# Sensors_AFE1.net
KiCad netlist of a schematic drawn in Altium Designer
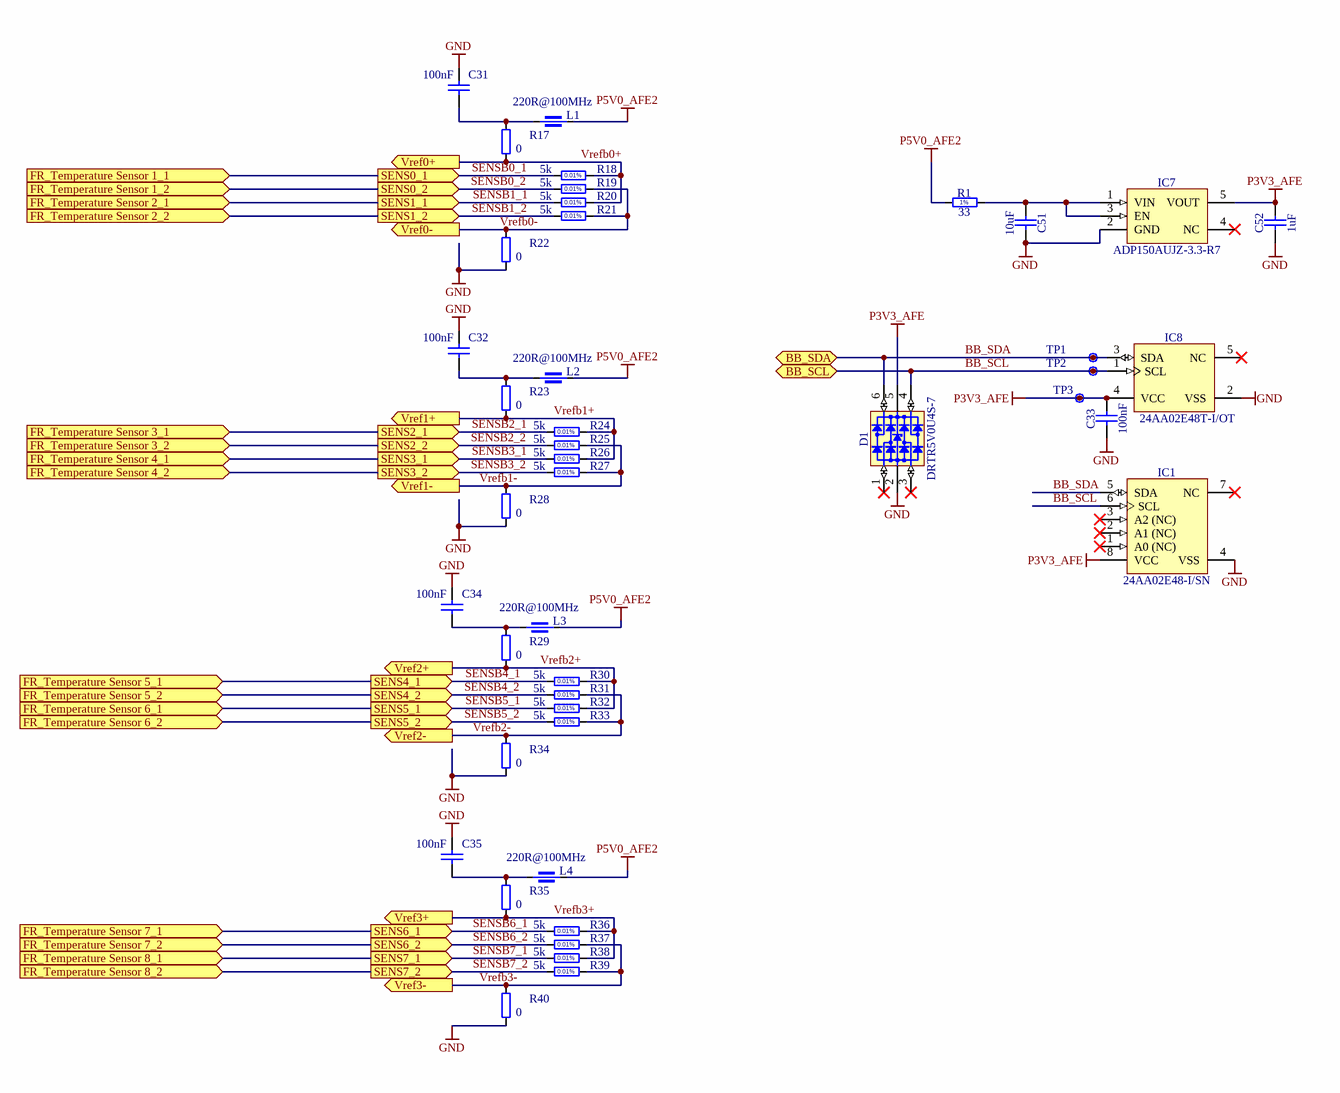
[diagram p0: Sensors_AFE1.schdoc]

(export (version "E")
  (design (tool "Eeschema 10.0.6"))
  (components
    (comp (ref "C31")
      (value "100nF")
      (footprint "CAPC1005X55N")
      (description "Non-polarised capacitor")
      (fields
        (field (name "PART NUMBER") "CC0402_100NF_16V_10%_X5R")
        (field (name "VOLTAGE") "16V")
        (field (name "AUTHOR") "CERN DEM JLC")
      )
      (libsource (lib "Capacitors") (part "Capacitor - non polarized"))
    )
    (comp (ref "C32")
      (value "100nF")
      (footprint "CAPC1005X55N")
      (description "Non-polarised capacitor")
      (fields
        (field (name "PART NUMBER") "CC0402_100NF_16V_10%_X5R")
        (field (name "VOLTAGE") "16V")
        (field (name "AUTHOR") "CERN DEM JLC")
      )
      (libsource (lib "Capacitors") (part "Capacitor - non polarized"))
    )
    (comp (ref "C33")
      (value "100nF")
      (footprint "CAPC1005X55N")
      (description "Non-polarised capacitor")
      (fields
        (field (name "PART NUMBER") "CC0402_100NF_16V_10%_X5R")
        (field (name "VOLTAGE") "16V")
        (field (name "AUTHOR") "CERN DEM JLC")
      )
      (libsource (lib "Capacitors") (part "Capacitor - non polarized"))
    )
    (comp (ref "C34")
      (value "100nF")
      (footprint "CAPC1005X55N")
      (description "Non-polarised capacitor")
      (fields
        (field (name "PART NUMBER") "CC0402_100NF_16V_10%_X5R")
        (field (name "VOLTAGE") "16V")
        (field (name "AUTHOR") "CERN DEM JLC")
      )
      (libsource (lib "Capacitors") (part "Capacitor - non polarized"))
    )
    (comp (ref "C35")
      (value "100nF")
      (footprint "CAPC1005X55N")
      (description "Non-polarised capacitor")
      (fields
        (field (name "PART NUMBER") "CC0402_100NF_16V_10%_X5R")
        (field (name "VOLTAGE") "16V")
        (field (name "AUTHOR") "CERN DEM JLC")
      )
      (libsource (lib "Capacitors") (part "Capacitor - non polarized"))
    )
    (comp (ref "C51")
      (value "10uF")
      (footprint "CAPC2012X135N")
      (description "Non-polarised capacitor")
      (fields
        (field (name "PART NUMBER") "CC0805_10UF_16V_10%_X5R")
        (field (name "VOLTAGE") "16V")
        (field (name "AUTHOR") "CERN DEM JLC")
      )
      (libsource (lib "Capacitors") (part "Capacitor - non polarized"))
    )
    (comp (ref "C52")
      (value "1uF")
      (footprint "CAPC1608X87N")
      (description "Non-polarised capacitor")
      (fields
        (field (name "PART NUMBER") "CC0603_1UF_25V_10%_X7R")
        (field (name "VOLTAGE") "25V")
        (field (name "AUTHOR") "CERN DEM JLC")
      )
      (libsource (lib "Capacitors") (part "Capacitor - non polarized"))
    )
    (comp (ref "D1")
      (value "DRTR5V0U4S-7")
      (footprint "SOT65P210X110-6N")
      (description "Integrated Quad Ultra-Low Capacitance ESD Protection")
      (fields (field (name "MANUFACTURER") "DIODES") (field (name "AUTHOR") "GK"))
      (libsource (lib "Diodes") (part "D_TVS_DRTR5V0U4S-7"))
    )
    (comp (ref "IC1")
      (value "24AA02E48-I/SN")
      (footprint "SOIC127P600X175-8N")
      (description "1.7V-5.5V, 2K I2C™ Serial EEPROMs with EUI-48™ Node Identity")
      (fields (field (name "MANUFACTURER") "MICROCHIP TECHNOLOGY") (field (name "AUTHOR") "CERN DEM MR"))
      (libsource (lib "ICS-logic") (part "MEM_24AA02E48-I/SN"))
    )
    (comp (ref "IC7")
      (value "ADP150AUJZ-3.3-R7")
      (footprint "SOT95P280X90-5N")
      (description "Ultralow Noise, 150 mA CMOS Linear Regulator")
      (fields (field (name "MANUFACTURER") "ANALOG DEVICES") (field (name "AUTHOR") "CERN DEM JLC"))
      (libsource (lib "ICs And Semiconductors") (part "ADP150AUJZ"))
    )
    (comp (ref "IC8")
      (value "24AA02E48T-I/OT")
      (footprint "SOT95P280X145-5N")
      (description "1.7V-5.5V, 2K I2C Serial EEPROM With EUI-48 Node Identity")
      (fields (field (name "MANUFACTURER") "MICROCHIP TECHNOLOGY") (field (name "AUTHOR") "CERN DEM MR"))
      (libsource (lib "ICs And Semiconductors") (part "24AA02E48T-I/OT"))
    )
    (comp (ref "L1")
      (value "220R@100MHz")
      (footprint "INDC1005X55N")
      (fields
        (field (name "PART NUMBER") "IND0402_MURATA_BLM15HB221SN1")
        (field (name "POWER") "250mA")
        (field (name "TOLERANCE") "±25%")
        (field (name "AUTHOR") "CERN DEM JLC")
      )
      (libsource (lib "Inductors & Transformers") (part "Ferrite Bead"))
    )
    (comp (ref "L2")
      (value "220R@100MHz")
      (footprint "INDC1005X55N")
      (fields
        (field (name "PART NUMBER") "IND0402_MURATA_BLM15HB221SN1")
        (field (name "POWER") "250mA")
        (field (name "TOLERANCE") "±25%")
        (field (name "AUTHOR") "CERN DEM JLC")
      )
      (libsource (lib "Inductors & Transformers") (part "Ferrite Bead"))
    )
    (comp (ref "L3")
      (value "220R@100MHz")
      (footprint "INDC1005X55N")
      (fields
        (field (name "PART NUMBER") "IND0402_MURATA_BLM15HB221SN1")
        (field (name "POWER") "250mA")
        (field (name "TOLERANCE") "±25%")
        (field (name "AUTHOR") "CERN DEM JLC")
      )
      (libsource (lib "Inductors & Transformers") (part "Ferrite Bead"))
    )
    (comp (ref "L4")
      (value "220R@100MHz")
      (footprint "INDC1005X55N")
      (fields
        (field (name "PART NUMBER") "IND0402_MURATA_BLM15HB221SN1")
        (field (name "POWER") "250mA")
        (field (name "TOLERANCE") "±25%")
        (field (name "AUTHOR") "CERN DEM JLC")
      )
      (libsource (lib "Inductors & Transformers") (part "Ferrite Bead"))
    )
    (comp (ref "R1")
      (value "33")
      (footprint "RESC1005X40N")
      (description "Resistor - 1%")
      (fields
        (field (name "PART NUMBER") "R0402_33R_1%_0.0625W_100PPM")
        (field (name "POWER") "0.0625W")
        (field (name "AUTHOR") "CERN DEM JLC")
      )
      (libsource (lib "Resistors") (part "Resistor - 1%"))
    )
    (comp (ref "R17")
      (value "0")
      (footprint "RESC1608X55N")
      (description "Resistor")
      (fields
        (field (name "PART NUMBER") "R0603_0R_JUMPER")
        (field (name "MANUFACTURER") "GENERIC")
        (field (name "AUTHOR") "CERN DEM JLC")
      )
      (libsource (lib "Resistors") (part "Resistor"))
    )
    (comp (ref "R18")
      (value "5k")
      (footprint "RESC2013X64N")
      (description "Resistor - 0.01%")
      (fields
        (field (name "PART NUMBER") "R0805_5K_0.01%_0.2W_0.2PPM_VISHAY_VSMP")
        (field (name "POWER") "0.2W")
        (field (name "AUTHOR") "CERN DEM JLC")
      )
      (libsource (lib "Resistors") (part "Resistor - 0.01%"))
    )
    (comp (ref "R19")
      (value "5k")
      (footprint "RESC2013X64N")
      (description "Resistor - 0.01%")
      (fields
        (field (name "PART NUMBER") "R0805_5K_0.01%_0.2W_0.2PPM_VISHAY_VSMP")
        (field (name "POWER") "0.2W")
        (field (name "AUTHOR") "CERN DEM JLC")
      )
      (libsource (lib "Resistors") (part "Resistor - 0.01%"))
    )
    (comp (ref "R20")
      (value "5k")
      (footprint "RESC2013X64N")
      (description "Resistor - 0.01%")
      (fields
        (field (name "PART NUMBER") "R0805_5K_0.01%_0.2W_0.2PPM_VISHAY_VSMP")
        (field (name "POWER") "0.2W")
        (field (name "AUTHOR") "CERN DEM JLC")
      )
      (libsource (lib "Resistors") (part "Resistor - 0.01%"))
    )
    (comp (ref "R21")
      (value "5k")
      (footprint "RESC2013X64N")
      (description "Resistor - 0.01%")
      (fields
        (field (name "PART NUMBER") "R0805_5K_0.01%_0.2W_0.2PPM_VISHAY_VSMP")
        (field (name "POWER") "0.2W")
        (field (name "AUTHOR") "CERN DEM JLC")
      )
      (libsource (lib "Resistors") (part "Resistor - 0.01%"))
    )
    (comp (ref "R22")
      (value "0")
      (footprint "RESC1608X55N")
      (description "Resistor")
      (fields
        (field (name "PART NUMBER") "R0603_0R_JUMPER")
        (field (name "MANUFACTURER") "GENERIC")
        (field (name "AUTHOR") "CERN DEM JLC")
      )
      (libsource (lib "Resistors") (part "Resistor"))
    )
    (comp (ref "R23")
      (value "0")
      (footprint "RESC1608X55N")
      (description "Resistor")
      (fields
        (field (name "PART NUMBER") "R0603_0R_JUMPER")
        (field (name "MANUFACTURER") "GENERIC")
        (field (name "AUTHOR") "CERN DEM JLC")
      )
      (libsource (lib "Resistors") (part "Resistor"))
    )
    (comp (ref "R24")
      (value "5k")
      (footprint "RESC2013X64N")
      (description "Resistor - 0.01%")
      (fields
        (field (name "PART NUMBER") "R0805_5K_0.01%_0.2W_0.2PPM_VISHAY_VSMP")
        (field (name "POWER") "0.2W")
        (field (name "AUTHOR") "CERN DEM JLC")
      )
      (libsource (lib "Resistors") (part "Resistor - 0.01%"))
    )
    (comp (ref "R25")
      (value "5k")
      (footprint "RESC2013X64N")
      (description "Resistor - 0.01%")
      (fields
        (field (name "PART NUMBER") "R0805_5K_0.01%_0.2W_0.2PPM_VISHAY_VSMP")
        (field (name "POWER") "0.2W")
        (field (name "AUTHOR") "CERN DEM JLC")
      )
      (libsource (lib "Resistors") (part "Resistor - 0.01%"))
    )
    (comp (ref "R26")
      (value "5k")
      (footprint "RESC2013X64N")
      (description "Resistor - 0.01%")
      (fields
        (field (name "PART NUMBER") "R0805_5K_0.01%_0.2W_0.2PPM_VISHAY_VSMP")
        (field (name "POWER") "0.2W")
        (field (name "AUTHOR") "CERN DEM JLC")
      )
      (libsource (lib "Resistors") (part "Resistor - 0.01%"))
    )
    (comp (ref "R27")
      (value "5k")
      (footprint "RESC2013X64N")
      (description "Resistor - 0.01%")
      (fields
        (field (name "PART NUMBER") "R0805_5K_0.01%_0.2W_0.2PPM_VISHAY_VSMP")
        (field (name "POWER") "0.2W")
        (field (name "AUTHOR") "CERN DEM JLC")
      )
      (libsource (lib "Resistors") (part "Resistor - 0.01%"))
    )
    (comp (ref "R28")
      (value "0")
      (footprint "RESC1608X55N")
      (description "Resistor")
      (fields
        (field (name "PART NUMBER") "R0603_0R_JUMPER")
        (field (name "MANUFACTURER") "GENERIC")
        (field (name "AUTHOR") "CERN DEM JLC")
      )
      (libsource (lib "Resistors") (part "Resistor"))
    )
    (comp (ref "R29")
      (value "0")
      (footprint "RESC1608X55N")
      (description "Resistor")
      (fields
        (field (name "PART NUMBER") "R0603_0R_JUMPER")
        (field (name "MANUFACTURER") "GENERIC")
        (field (name "AUTHOR") "CERN DEM JLC")
      )
      (libsource (lib "Resistors") (part "Resistor"))
    )
    (comp (ref "R30")
      (value "5k")
      (footprint "RESC2013X64N")
      (description "Resistor - 0.01%")
      (fields
        (field (name "PART NUMBER") "R0805_5K_0.01%_0.2W_0.2PPM_VISHAY_VSMP")
        (field (name "POWER") "0.2W")
        (field (name "AUTHOR") "CERN DEM JLC")
      )
      (libsource (lib "Resistors") (part "Resistor - 0.01%"))
    )
    (comp (ref "R31")
      (value "5k")
      (footprint "RESC2013X64N")
      (description "Resistor - 0.01%")
      (fields
        (field (name "PART NUMBER") "R0805_5K_0.01%_0.2W_0.2PPM_VISHAY_VSMP")
        (field (name "POWER") "0.2W")
        (field (name "AUTHOR") "CERN DEM JLC")
      )
      (libsource (lib "Resistors") (part "Resistor - 0.01%"))
    )
    (comp (ref "R32")
      (value "5k")
      (footprint "RESC2013X64N")
      (description "Resistor - 0.01%")
      (fields
        (field (name "PART NUMBER") "R0805_5K_0.01%_0.2W_0.2PPM_VISHAY_VSMP")
        (field (name "POWER") "0.2W")
        (field (name "AUTHOR") "CERN DEM JLC")
      )
      (libsource (lib "Resistors") (part "Resistor - 0.01%"))
    )
    (comp (ref "R33")
      (value "5k")
      (footprint "RESC2013X64N")
      (description "Resistor - 0.01%")
      (fields
        (field (name "PART NUMBER") "R0805_5K_0.01%_0.2W_0.2PPM_VISHAY_VSMP")
        (field (name "POWER") "0.2W")
        (field (name "AUTHOR") "CERN DEM JLC")
      )
      (libsource (lib "Resistors") (part "Resistor - 0.01%"))
    )
    (comp (ref "R34")
      (value "0")
      (footprint "RESC1608X55N")
      (description "Resistor")
      (fields
        (field (name "PART NUMBER") "R0603_0R_JUMPER")
        (field (name "MANUFACTURER") "GENERIC")
        (field (name "AUTHOR") "CERN DEM JLC")
      )
      (libsource (lib "Resistors") (part "Resistor"))
    )
    (comp (ref "R35")
      (value "0")
      (footprint "RESC1608X55N")
      (description "Resistor")
      (fields
        (field (name "PART NUMBER") "R0603_0R_JUMPER")
        (field (name "MANUFACTURER") "GENERIC")
        (field (name "AUTHOR") "CERN DEM JLC")
      )
      (libsource (lib "Resistors") (part "Resistor"))
    )
    (comp (ref "R36")
      (value "5k")
      (footprint "RESC2013X64N")
      (description "Resistor - 0.01%")
      (fields
        (field (name "PART NUMBER") "R0805_5K_0.01%_0.2W_0.2PPM_VISHAY_VSMP")
        (field (name "POWER") "0.2W")
        (field (name "AUTHOR") "CERN DEM JLC")
      )
      (libsource (lib "Resistors") (part "Resistor - 0.01%"))
    )
    (comp (ref "R37")
      (value "5k")
      (footprint "RESC2013X64N")
      (description "Resistor - 0.01%")
      (fields
        (field (name "PART NUMBER") "R0805_5K_0.01%_0.2W_0.2PPM_VISHAY_VSMP")
        (field (name "POWER") "0.2W")
        (field (name "AUTHOR") "CERN DEM JLC")
      )
      (libsource (lib "Resistors") (part "Resistor - 0.01%"))
    )
    (comp (ref "R38")
      (value "5k")
      (footprint "RESC2013X64N")
      (description "Resistor - 0.01%")
      (fields
        (field (name "PART NUMBER") "R0805_5K_0.01%_0.2W_0.2PPM_VISHAY_VSMP")
        (field (name "POWER") "0.2W")
        (field (name "AUTHOR") "CERN DEM JLC")
      )
      (libsource (lib "Resistors") (part "Resistor - 0.01%"))
    )
    (comp (ref "R39")
      (value "5k")
      (footprint "RESC2013X64N")
      (description "Resistor - 0.01%")
      (fields
        (field (name "PART NUMBER") "R0805_5K_0.01%_0.2W_0.2PPM_VISHAY_VSMP")
        (field (name "POWER") "0.2W")
        (field (name "AUTHOR") "CERN DEM JLC")
      )
      (libsource (lib "Resistors") (part "Resistor - 0.01%"))
    )
    (comp (ref "R40")
      (value "0")
      (footprint "RESC1608X55N")
      (description "Resistor")
      (fields
        (field (name "PART NUMBER") "R0603_0R_JUMPER")
        (field (name "MANUFACTURER") "GENERIC")
        (field (name "AUTHOR") "CERN DEM JLC")
      )
      (libsource (lib "Resistors") (part "Resistor"))
    )
    (comp (ref "TP1")
      (value "Test Point")
      (footprint "TPS127")
      (fields (field (name "PART NUMBER") "SMD_PAD_1.27X1.27MM") (field (name "AUTHOR") "CERN DEM JLC"))
      (libsource (lib "Eletro-mechanical") (part "Test Point"))
    )
    (comp (ref "TP2")
      (value "Test Point")
      (footprint "TPS127")
      (fields (field (name "PART NUMBER") "SMD_PAD_1.27X1.27MM") (field (name "AUTHOR") "CERN DEM JLC"))
      (libsource (lib "Eletro-mechanical") (part "Test Point"))
    )
    (comp (ref "TP3")
      (value "Test Point")
      (footprint "TPS127")
      (fields (field (name "PART NUMBER") "SMD_PAD_1.27X1.27MM") (field (name "AUTHOR") "CERN DEM JLC"))
      (libsource (lib "Eletro-mechanical") (part "Test Point"))
    )
  )
  (nets
    (net (code "1") (name "/BB_SCL") (class "Default")
      (node (ref "D1") (pin "4") (pinfunction "I/O3_4") (pintype "bidirectional"))
      (node (ref "IC1") (pin "6") (pinfunction "SCL_6") (pintype "input"))
      (node (ref "IC8") (pin "1") (pinfunction "SCL_1") (pintype "input"))
      (node (ref "TP2") (pin "1") (pinfunction "1_1") (pintype "bidirectional"))
    )
    (net (code "2") (name "/BB_SDA") (class "Default")
      (node (ref "D1") (pin "6") (pinfunction "I/O4_6") (pintype "bidirectional"))
      (node (ref "IC1") (pin "5") (pinfunction "SDA_5") (pintype "bidirectional"))
      (node (ref "IC8") (pin "3") (pinfunction "SDA_3") (pintype "bidirectional"))
      (node (ref "TP1") (pin "1") (pinfunction "1_1") (pintype "bidirectional"))
    )
    (net (code "3") (name "/SENSB0_1") (class "Default")
      (node (ref "R18") (pin "1") (pinfunction "1_1") (pintype "passive"))
    )
    (net (code "4") (name "/SENSB0_2") (class "Default")
      (node (ref "R19") (pin "1") (pinfunction "1_1") (pintype "passive"))
    )
    (net (code "5") (name "/SENSB1_1") (class "Default")
      (node (ref "R20") (pin "1") (pinfunction "1_1") (pintype "passive"))
    )
    (net (code "6") (name "/SENSB1_2") (class "Default")
      (node (ref "R21") (pin "1") (pinfunction "1_1") (pintype "passive"))
    )
    (net (code "7") (name "/SENSB2_1") (class "Default")
      (node (ref "R24") (pin "1") (pinfunction "1_1") (pintype "passive"))
    )
    (net (code "8") (name "/SENSB2_2") (class "Default")
      (node (ref "R25") (pin "1") (pinfunction "1_1") (pintype "passive"))
    )
    (net (code "9") (name "/SENSB3_1") (class "Default")
      (node (ref "R26") (pin "1") (pinfunction "1_1") (pintype "passive"))
    )
    (net (code "10") (name "/SENSB3_2") (class "Default")
      (node (ref "R27") (pin "1") (pinfunction "1_1") (pintype "passive"))
    )
    (net (code "11") (name "/SENSB4_1") (class "Default")
      (node (ref "R30") (pin "1") (pinfunction "1_1") (pintype "passive"))
    )
    (net (code "12") (name "/SENSB4_2") (class "Default")
      (node (ref "R31") (pin "1") (pinfunction "1_1") (pintype "passive"))
    )
    (net (code "13") (name "/SENSB5_1") (class "Default")
      (node (ref "R32") (pin "1") (pinfunction "1_1") (pintype "passive"))
    )
    (net (code "14") (name "/SENSB5_2") (class "Default")
      (node (ref "R33") (pin "1") (pinfunction "1_1") (pintype "passive"))
    )
    (net (code "15") (name "/SENSB6_1") (class "Default")
      (node (ref "R36") (pin "1") (pinfunction "1_1") (pintype "passive"))
    )
    (net (code "16") (name "/SENSB6_2") (class "Default")
      (node (ref "R37") (pin "1") (pinfunction "1_1") (pintype "passive"))
    )
    (net (code "17") (name "/SENSB7_1") (class "Default")
      (node (ref "R38") (pin "1") (pinfunction "1_1") (pintype "passive"))
    )
    (net (code "18") (name "/SENSB7_2") (class "Default")
      (node (ref "R39") (pin "1") (pinfunction "1_1") (pintype "passive"))
    )
    (net (code "19") (name "/Vrefb0+") (class "Default")
      (node (ref "R17") (pin "1") (pinfunction "1_1") (pintype "passive"))
      (node (ref "R18") (pin "2") (pinfunction "2_2") (pintype "passive"))
      (node (ref "R20") (pin "2") (pinfunction "2_2") (pintype "passive"))
    )
    (net (code "20") (name "/Vrefb0-") (class "Default")
      (node (ref "R19") (pin "2") (pinfunction "2_2") (pintype "passive"))
      (node (ref "R21") (pin "2") (pinfunction "2_2") (pintype "passive"))
      (node (ref "R22") (pin "2") (pinfunction "2_2") (pintype "passive"))
    )
    (net (code "21") (name "/Vrefb1+") (class "Default")
      (node (ref "R23") (pin "1") (pinfunction "1_1") (pintype "passive"))
      (node (ref "R24") (pin "2") (pinfunction "2_2") (pintype "passive"))
      (node (ref "R26") (pin "2") (pinfunction "2_2") (pintype "passive"))
    )
    (net (code "22") (name "/Vrefb1-") (class "Default")
      (node (ref "R25") (pin "2") (pinfunction "2_2") (pintype "passive"))
      (node (ref "R27") (pin "2") (pinfunction "2_2") (pintype "passive"))
      (node (ref "R28") (pin "2") (pinfunction "2_2") (pintype "passive"))
    )
    (net (code "23") (name "/Vrefb2+") (class "Default")
      (node (ref "R29") (pin "1") (pinfunction "1_1") (pintype "passive"))
      (node (ref "R30") (pin "2") (pinfunction "2_2") (pintype "passive"))
      (node (ref "R32") (pin "2") (pinfunction "2_2") (pintype "passive"))
    )
    (net (code "24") (name "/Vrefb2-") (class "Default")
      (node (ref "R31") (pin "2") (pinfunction "2_2") (pintype "passive"))
      (node (ref "R33") (pin "2") (pinfunction "2_2") (pintype "passive"))
      (node (ref "R34") (pin "2") (pinfunction "2_2") (pintype "passive"))
    )
    (net (code "25") (name "/Vrefb3+") (class "Default")
      (node (ref "R35") (pin "1") (pinfunction "1_1") (pintype "passive"))
      (node (ref "R36") (pin "2") (pinfunction "2_2") (pintype "passive"))
      (node (ref "R38") (pin "2") (pinfunction "2_2") (pintype "passive"))
    )
    (net (code "26") (name "/Vrefb3-") (class "Default")
      (node (ref "R37") (pin "2") (pinfunction "2_2") (pintype "passive"))
      (node (ref "R39") (pin "2") (pinfunction "2_2") (pintype "passive"))
      (node (ref "R40") (pin "2") (pinfunction "2_2") (pintype "passive"))
    )
    (net (code "27") (name "GND") (class "Default")
      (node (ref "C31") (pin "1") (pinfunction "1_1") (pintype "passive"))
      (node (ref "C32") (pin "1") (pinfunction "1_1") (pintype "passive"))
      (node (ref "C33") (pin "1") (pinfunction "1_1") (pintype "passive"))
      (node (ref "C34") (pin "1") (pinfunction "1_1") (pintype "passive"))
      (node (ref "C35") (pin "1") (pinfunction "1_1") (pintype "passive"))
      (node (ref "C51") (pin "2") (pinfunction "2_2") (pintype "passive"))
      (node (ref "C52") (pin "1") (pinfunction "1_1") (pintype "passive"))
      (node (ref "D1") (pin "2") (pinfunction "GND_2") (pintype "power_in"))
      (node (ref "IC1") (pin "4") (pinfunction "VSS_4") (pintype "power_in"))
      (node (ref "IC7") (pin "2") (pinfunction "GND_2") (pintype "power_in"))
      (node (ref "IC8") (pin "2") (pinfunction "VSS_2") (pintype "power_in"))
      (node (ref "R22") (pin "1") (pinfunction "1_1") (pintype "passive"))
      (node (ref "R28") (pin "1") (pinfunction "1_1") (pintype "passive"))
      (node (ref "R34") (pin "1") (pinfunction "1_1") (pintype "passive"))
      (node (ref "R40") (pin "1") (pinfunction "1_1") (pintype "passive"))
    )
    (net (code "28") (name "Net-(C31-Pad2)") (class "Default")
      (node (ref "C31") (pin "2") (pinfunction "2_2") (pintype "passive"))
      (node (ref "L1") (pin "1") (pinfunction "1_1") (pintype "passive"))
      (node (ref "R17") (pin "2") (pinfunction "2_2") (pintype "passive"))
    )
    (net (code "29") (name "Net-(C32-Pad2)") (class "Default")
      (node (ref "C32") (pin "2") (pinfunction "2_2") (pintype "passive"))
      (node (ref "L2") (pin "1") (pinfunction "1_1") (pintype "passive"))
      (node (ref "R23") (pin "2") (pinfunction "2_2") (pintype "passive"))
    )
    (net (code "30") (name "Net-(C34-Pad2)") (class "Default")
      (node (ref "C34") (pin "2") (pinfunction "2_2") (pintype "passive"))
      (node (ref "L3") (pin "1") (pinfunction "1_1") (pintype "passive"))
      (node (ref "R29") (pin "2") (pinfunction "2_2") (pintype "passive"))
    )
    (net (code "31") (name "Net-(C35-Pad2)") (class "Default")
      (node (ref "C35") (pin "2") (pinfunction "2_2") (pintype "passive"))
      (node (ref "L4") (pin "1") (pinfunction "1_1") (pintype "passive"))
      (node (ref "R35") (pin "2") (pinfunction "2_2") (pintype "passive"))
    )
    (net (code "32") (name "Net-(IC7-EN)") (class "Default")
      (node (ref "C51") (pin "1") (pinfunction "1_1") (pintype "passive"))
      (node (ref "IC7") (pin "1") (pinfunction "VIN_1") (pintype "input"))
      (node (ref "IC7") (pin "3") (pinfunction "EN_3") (pintype "input"))
      (node (ref "R1") (pin "2") (pinfunction "2_2") (pintype "passive"))
    )
    (net (code "33") (name "P3V3_AFE") (class "Default")
      (node (ref "C33") (pin "2") (pinfunction "2_2") (pintype "passive"))
      (node (ref "C52") (pin "2") (pinfunction "2_2") (pintype "passive"))
      (node (ref "D1") (pin "5") (pinfunction "VBUS_5") (pintype "power_in"))
      (node (ref "IC1") (pin "8") (pinfunction "VCC_8") (pintype "power_in"))
      (node (ref "IC7") (pin "5") (pinfunction "VOUT_5") (pintype "power_in"))
      (node (ref "IC8") (pin "4") (pinfunction "VCC_4") (pintype "power_in"))
      (node (ref "TP3") (pin "1") (pinfunction "1_1") (pintype "bidirectional"))
    )
    (net (code "34") (name "P5V0_AFE2") (class "Default")
      (node (ref "L1") (pin "2") (pinfunction "2_2") (pintype "passive"))
      (node (ref "L2") (pin "2") (pinfunction "2_2") (pintype "passive"))
      (node (ref "L3") (pin "2") (pinfunction "2_2") (pintype "passive"))
      (node (ref "L4") (pin "2") (pinfunction "2_2") (pintype "passive"))
      (node (ref "R1") (pin "1") (pinfunction "1_1") (pintype "passive"))
    )
    (net (code "35") (name "unconnected-(D1-I{slash}O1-Pad1)") (class "Default")
      (node (ref "D1") (pin "1") (pinfunction "I/O1_1") (pintype "bidirectional+no_connect"))
    )
    (net (code "36") (name "unconnected-(D1-I{slash}O2-Pad3)") (class "Default")
      (node (ref "D1") (pin "3") (pinfunction "I/O2_3") (pintype "bidirectional+no_connect"))
    )
    (net (code "37") (name "unconnected-(IC1-A0_(NC)-Pad1)") (class "Default")
      (node (ref "IC1") (pin "1") (pinfunction "A0_(NC)_1") (pintype "input+no_connect"))
    )
    (net (code "38") (name "unconnected-(IC1-A1_(NC)-Pad2)") (class "Default")
      (node (ref "IC1") (pin "2") (pinfunction "A1_(NC)_2") (pintype "input+no_connect"))
    )
    (net (code "39") (name "unconnected-(IC1-A2_(NC)-Pad3)") (class "Default")
      (node (ref "IC1") (pin "3") (pinfunction "A2_(NC)_3") (pintype "input+no_connect"))
    )
    (net (code "40") (name "unconnected-(IC1-NC-Pad7)") (class "Default")
      (node (ref "IC1") (pin "7") (pinfunction "NC_7") (pintype "passive+no_connect"))
    )
    (net (code "41") (name "unconnected-(IC7-NC-Pad4)") (class "Default")
      (node (ref "IC7") (pin "4") (pinfunction "NC_4") (pintype "passive+no_connect"))
    )
    (net (code "42") (name "unconnected-(IC8-NC-Pad5)") (class "Default")
      (node (ref "IC8") (pin "5") (pinfunction "NC_5") (pintype "passive+no_connect"))
    )
  )
)
